# TouScruino-avr-v0.net
KiCad netlist of a schematic drawn in EAGLE
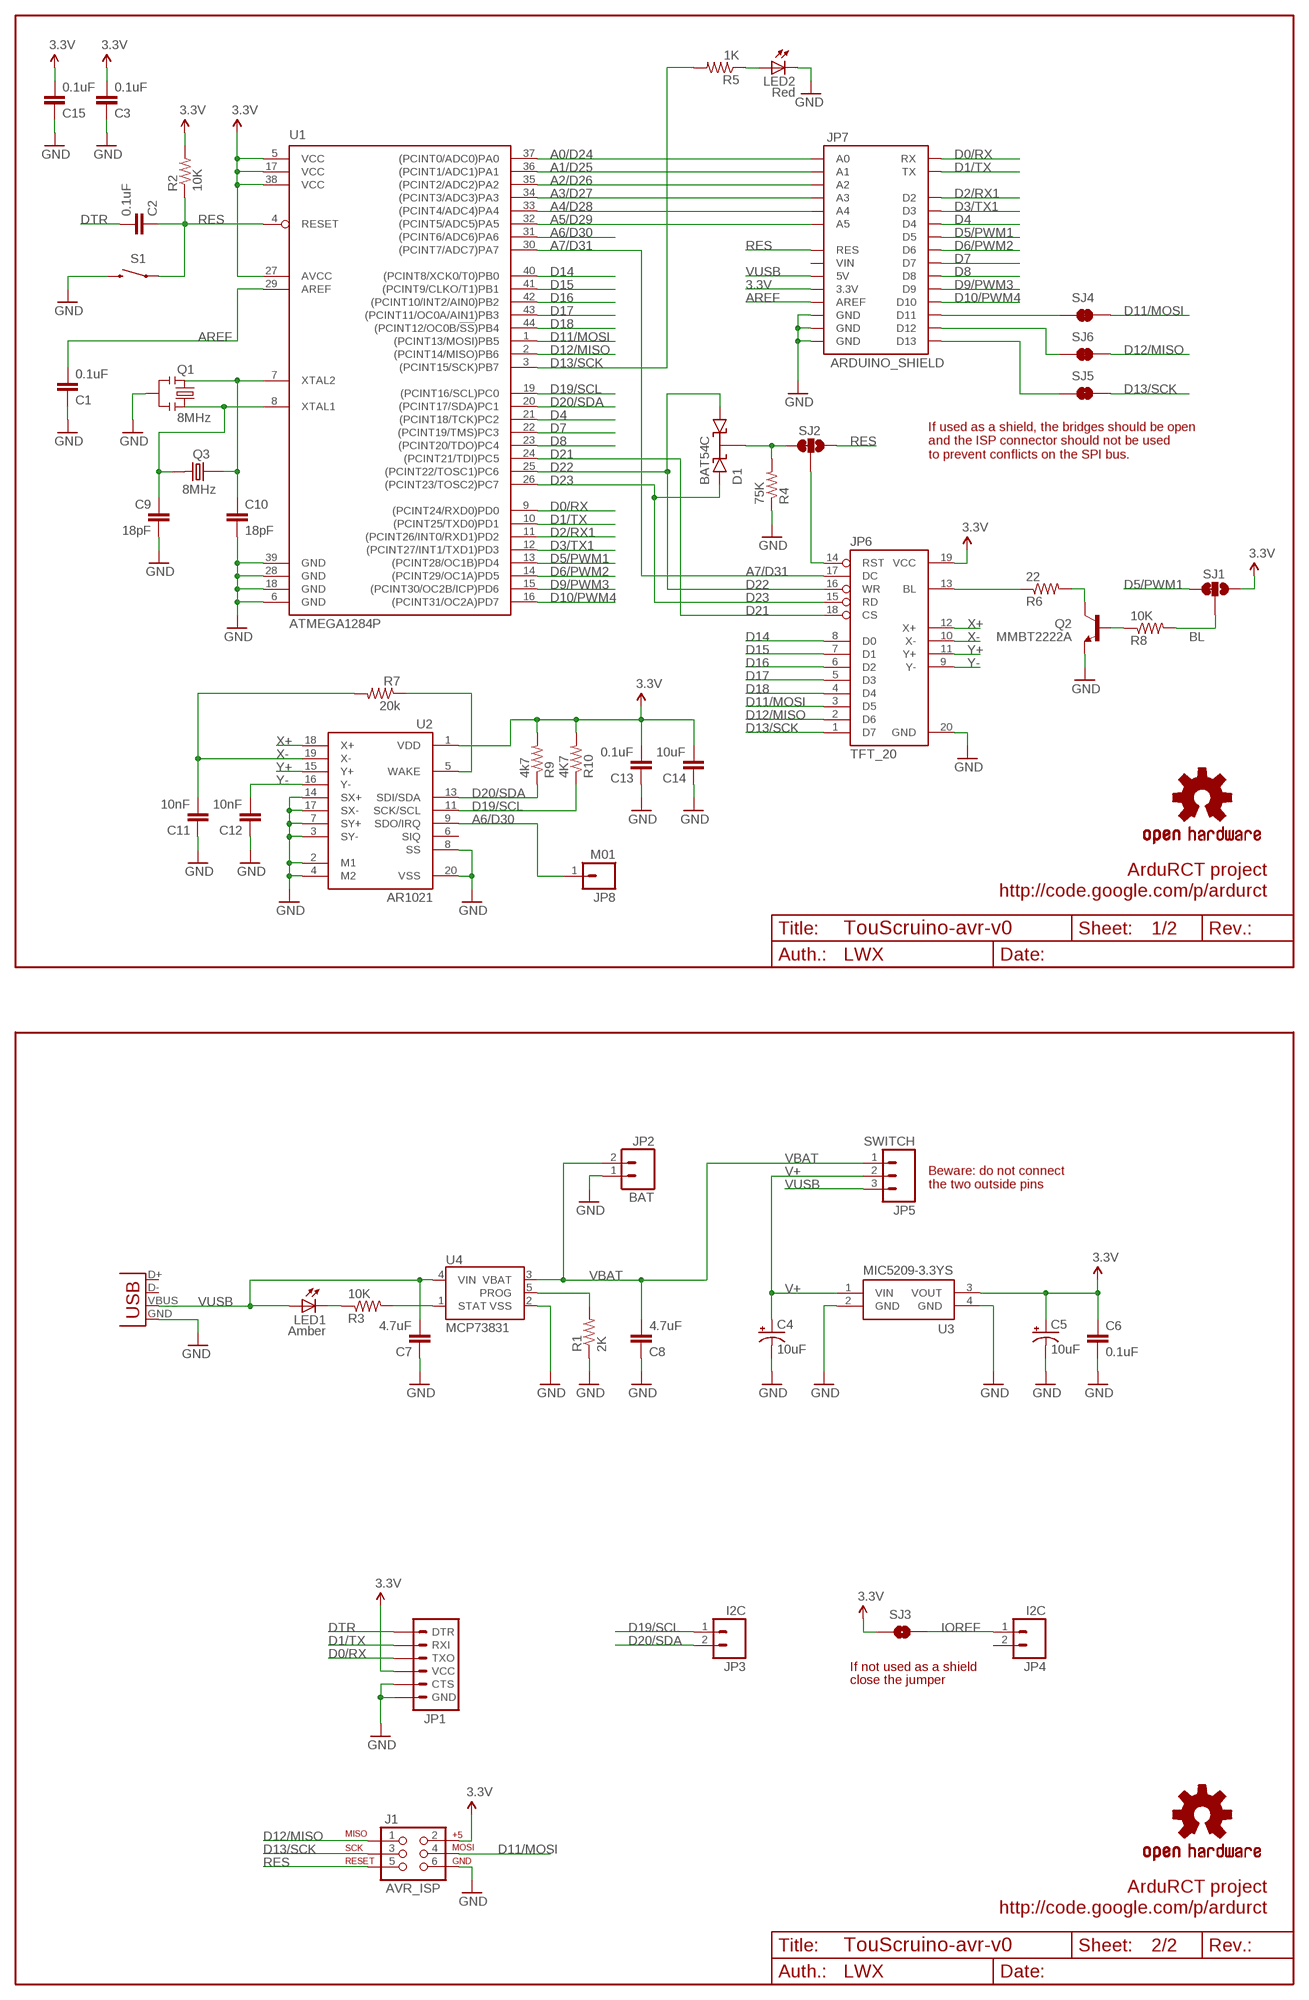
[diagram p0: schematic, sheet 1]

(export (version "E")
  (design (tool "Eeschema 10.0.6"))
  (components
    (comp (ref "C1")
      (value "0.1uF")
      (footprint "eagle-import:0805")
      (libsource (lib "eagle-import") (part "CAP0805"))
    )
    (comp (ref "C2")
      (value "0.1uF")
      (footprint "eagle-import:0805")
      (libsource (lib "eagle-import") (part "CAP0805"))
    )
    (comp (ref "C3")
      (value "0.1uF")
      (footprint "eagle-import:0805")
      (libsource (lib "eagle-import") (part "CAP0805"))
    )
    (comp (ref "C4")
      (value "10uF")
      (footprint "eagle-import:EIA3216")
      (libsource (lib "eagle-import") (part "CAP_POL1206"))
    )
    (comp (ref "C5")
      (value "10uF")
      (footprint "eagle-import:EIA3216")
      (libsource (lib "eagle-import") (part "CAP_POL1206"))
    )
    (comp (ref "C6")
      (value "0.1uF")
      (footprint "eagle-import:0805")
      (libsource (lib "eagle-import") (part "CAP0805"))
    )
    (comp (ref "C7")
      (value "4.7uF")
      (footprint "eagle-import:0805")
      (libsource (lib "eagle-import") (part "CAP0805"))
    )
    (comp (ref "C8")
      (value "4.7uF")
      (footprint "eagle-import:0805")
      (libsource (lib "eagle-import") (part "CAP0805"))
    )
    (comp (ref "C9")
      (value "18pF")
      (footprint "eagle-import:0603-CAP")
      (libsource (lib "eagle-import") (part "CAP0603-CAP"))
    )
    (comp (ref "C10")
      (value "18pF")
      (footprint "eagle-import:0603-CAP")
      (libsource (lib "eagle-import") (part "CAP0603-CAP"))
    )
    (comp (ref "C11")
      (value "10nF")
      (footprint "eagle-import:0805")
      (libsource (lib "eagle-import") (part "CAP0805"))
    )
    (comp (ref "C12")
      (value "10nF")
      (footprint "eagle-import:0805")
      (libsource (lib "eagle-import") (part "CAP0805"))
    )
    (comp (ref "C13")
      (value "0.1uF")
      (footprint "eagle-import:0805")
      (libsource (lib "eagle-import") (part "CAP0805"))
    )
    (comp (ref "C14")
      (value "10uF")
      (footprint "eagle-import:0805")
      (libsource (lib "eagle-import") (part "CAP0805"))
    )
    (comp (ref "C15")
      (value "0.1uF")
      (footprint "eagle-import:0805")
      (libsource (lib "eagle-import") (part "CAP0805"))
    )
    (comp (ref "D1")
      (value "BAT54C")
      (footprint "eagle-import:SOT23-3")
      (libsource (lib "eagle-import") (part "BAT54C"))
    )
    (comp (ref "J1")
      (value "AVR_ISP")
      (footprint "eagle-import:2X3")
      (libsource (lib "eagle-import") (part "AVR_SPI_PRG_6PTH"))
    )
    (comp (ref "JP1")
      (value "ARDUINO_SERIAL_PROGRAMPTH")
      (footprint "eagle-import:1X06")
      (libsource (lib "eagle-import") (part "ARDUINO_SERIAL_PROGRAMPTH"))
    )
    (comp (ref "JP2")
      (value "BAT")
      (footprint "eagle-import:JST-2-SMD")
      (libsource (lib "eagle-import") (part "M02-JST-2MM-SMT"))
    )
    (comp (ref "JP3")
      (value "I2C")
      (footprint "eagle-import:1X02")
      (libsource (lib "eagle-import") (part "M02"))
    )
    (comp (ref "JP4")
      (value "I2C")
      (footprint "eagle-import:1X02")
      (libsource (lib "eagle-import") (part "M02"))
    )
    (comp (ref "JP5")
      (value "SWITCH")
      (footprint "eagle-import:1X3_LONGPAD")
      (libsource (lib "eagle-import") (part "M03"))
    )
    (comp (ref "JP6")
      (value "TFT_20")
      (footprint "eagle-import:TFT_20")
      (libsource (lib "eagle-import") (part "TFT_20"))
    )
    (comp (ref "JP7")
      (value "ARDUINO_SHIELD")
      (footprint "eagle-import:ARDUINO_SHIELD")
      (libsource (lib "eagle-import") (part "ARDUINO_SHIELD"))
    )
    (comp (ref "JP8")
      (value "M01")
      (footprint "eagle-import:1X1")
      (libsource (lib "eagle-import") (part "M01"))
    )
    (comp (ref "LED1")
      (value "Amber")
      (footprint "eagle-import:LED")
      (libsource (lib "eagle-import") (part "LED"))
    )
    (comp (ref "LED2")
      (value "Red")
      (footprint "eagle-import:LED")
      (libsource (lib "eagle-import") (part "LED"))
    )
    (comp (ref "Q1")
      (value "8MHz")
      (footprint "eagle-import:RESONATOR-SMD")
      (libsource (lib "eagle-import") (part "RESONATORSMD"))
    )
    (comp (ref "Q2")
      (value "MMBT2222A")
      (footprint "eagle-import:SOT23-3")
      (libsource (lib "eagle-import") (part "TRANSISTOR_NPNSOT23-3"))
    )
    (comp (ref "Q3")
      (value "8MHz")
      (footprint "eagle-import:CRYSTAL_5X3.2")
      (libsource (lib "eagle-import") (part "CRYSTAL_5X3.2"))
    )
    (comp (ref "R1")
      (value "2K")
      (footprint "eagle-import:0805")
      (libsource (lib "eagle-import") (part "RESISTOR0805-RES"))
    )
    (comp (ref "R2")
      (value "10K")
      (footprint "eagle-import:0805")
      (libsource (lib "eagle-import") (part "RESISTOR0805-RES"))
    )
    (comp (ref "R3")
      (value "10K")
      (footprint "eagle-import:0805")
      (libsource (lib "eagle-import") (part "RESISTOR0805-RES"))
    )
    (comp (ref "R4")
      (value "75K")
      (footprint "eagle-import:0805")
      (libsource (lib "eagle-import") (part "RESISTOR0805-RES"))
    )
    (comp (ref "R5")
      (value "1K")
      (footprint "eagle-import:0805")
      (libsource (lib "eagle-import") (part "RESISTOR0805-RES"))
    )
    (comp (ref "R6")
      (value "22")
      (footprint "eagle-import:0805")
      (libsource (lib "eagle-import") (part "RESISTOR0805-RES"))
    )
    (comp (ref "R7")
      (value "20k")
      (footprint "eagle-import:0805")
      (libsource (lib "eagle-import") (part "RESISTOR0805-RES"))
    )
    (comp (ref "R8")
      (value "10K")
      (footprint "eagle-import:0805")
      (libsource (lib "eagle-import") (part "RESISTOR0805-RES"))
    )
    (comp (ref "R9")
      (value "4k7")
      (footprint "eagle-import:0805")
      (libsource (lib "eagle-import") (part "RESISTOR0805-RES"))
    )
    (comp (ref "R10")
      (value "4K7")
      (footprint "eagle-import:0805")
      (libsource (lib "eagle-import") (part "RESISTOR0805-RES"))
    )
    (comp (ref "S1")
      (value "SWITCH-MOMENTARY-2SMD")
      (footprint "eagle-import:TACTILE_SWITCH_SMD")
      (libsource (lib "eagle-import") (part "SWITCH-MOMENTARY-2SMD"))
    )
    (comp (ref "SJ1")
      (value "SJ_2WAYS_1-2")
      (footprint "eagle-import:SJ_2WAYS_1-2_S")
      (libsource (lib "eagle-import") (part "SJ_2WAYS_1-2"))
    )
    (comp (ref "SJ2")
      (value "SJ_2WAYS_1-2")
      (footprint "eagle-import:SJ_2WAYS_1-2_S")
      (libsource (lib "eagle-import") (part "SJ_2WAYS_1-2"))
    )
    (comp (ref "SJ3")
      (value "SOLDERJUMPERNO")
      (footprint "eagle-import:SJ_2S-NO")
      (libsource (lib "eagle-import") (part "SOLDERJUMPERNO"))
    )
    (comp (ref "SJ4")
      (value "SOLDERJUMPERTRACE")
      (footprint "eagle-import:SJ_2S-TRACE")
      (libsource (lib "eagle-import") (part "SOLDERJUMPERTRACE"))
    )
    (comp (ref "SJ5")
      (value "SOLDERJUMPERTRACE")
      (footprint "eagle-import:SJ_2S-TRACE")
      (libsource (lib "eagle-import") (part "SOLDERJUMPERTRACE"))
    )
    (comp (ref "SJ6")
      (value "SOLDERJUMPERTRACE")
      (footprint "eagle-import:SJ_2S-TRACE")
      (libsource (lib "eagle-import") (part "SOLDERJUMPERTRACE"))
    )
    (comp (ref "U$3")
      (value "OSHW-LOGOM")
      (footprint "eagle-import:OSHW-LOGO-M")
      (libsource (lib "eagle-import") (part "OSHW-LOGOM"))
    )
    (comp (ref "U$5")
      (value "OSHW-LOGOM")
      (footprint "eagle-import:OSHW-LOGO-M")
      (libsource (lib "eagle-import") (part "OSHW-LOGOM"))
    )
    (comp (ref "U1")
      (value "ATMEGA1284P")
      (footprint "eagle-import:TQFP44")
      (libsource (lib "eagle-import") (part "ATMEGA324A"))
    )
    (comp (ref "U2")
      (value "AR1021")
      (footprint "eagle-import:SSOP20")
      (libsource (lib "eagle-import") (part "AR1020"))
    )
    (comp (ref "U3")
      (value "MIC5209-3.3YS")
      (footprint "eagle-import:SOT223")
      (libsource (lib "eagle-import") (part "MIC5209"))
    )
    (comp (ref "U4")
      (value "MCP73831")
      (footprint "eagle-import:SOT23-5")
      (libsource (lib "eagle-import") (part "MCP73831"))
    )
    (comp (ref "X2")
      (value "USB-MICROB")
      (footprint "eagle-import:USB-MICROB")
      (libsource (lib "eagle-import") (part "USB-MICROB"))
    )
  )
  (nets
    (net (code "1") (name "/A0{slash}D24") (class "Default")
      (node (ref "JP7") (pin "A0") (pinfunction "A0_A0") (pintype "bidirectional"))
      (node (ref "U1") (pin "37") (pinfunction "(PCINT0/ADC0)PA0_37") (pintype "bidirectional"))
    )
    (net (code "2") (name "/A1{slash}D25") (class "Default")
      (node (ref "JP7") (pin "A1") (pinfunction "A1_A1") (pintype "bidirectional"))
      (node (ref "U1") (pin "36") (pinfunction "(PCINT1/ADC1)PA1_36") (pintype "bidirectional"))
    )
    (net (code "3") (name "/A2{slash}D26") (class "Default")
      (node (ref "JP7") (pin "A2") (pinfunction "A2_A2") (pintype "bidirectional"))
      (node (ref "U1") (pin "35") (pinfunction "(PCINT2/ADC2)PA2_35") (pintype "bidirectional"))
    )
    (net (code "4") (name "/A3{slash}D27") (class "Default")
      (node (ref "JP7") (pin "A3") (pinfunction "A3_A3") (pintype "bidirectional"))
      (node (ref "U1") (pin "34") (pinfunction "(PCINT3/ADC3)PA3_34") (pintype "bidirectional"))
    )
    (net (code "5") (name "/A4{slash}D28") (class "Default")
      (node (ref "JP7") (pin "A4") (pinfunction "A4_A4") (pintype "bidirectional"))
      (node (ref "U1") (pin "33") (pinfunction "(PCINT4/ADC4)PA4_33") (pintype "bidirectional"))
    )
    (net (code "6") (name "/A5{slash}D29") (class "Default")
      (node (ref "JP7") (pin "A5") (pinfunction "A5_A5") (pintype "bidirectional"))
      (node (ref "U1") (pin "32") (pinfunction "(PCINT5/ADC5)PA5_32") (pintype "bidirectional"))
    )
    (net (code "7") (name "/A6{slash}D30") (class "Default")
      (node (ref "JP8") (pin "1") (pinfunction "1_1") (pintype "passive"))
      (node (ref "U1") (pin "31") (pinfunction "(PCINT6/ADC6)PA6_31") (pintype "bidirectional"))
      (node (ref "U2") (pin "9") (pinfunction "SDO/IRQ_9") (pintype "bidirectional"))
    )
    (net (code "8") (name "/A7{slash}D31") (class "Default")
      (node (ref "JP6") (pin "17") (pinfunction "DC_17") (pintype "bidirectional"))
      (node (ref "U1") (pin "30") (pinfunction "(PCINT7/ADC7)PA7_30") (pintype "bidirectional"))
    )
    (net (code "9") (name "/AREF") (class "Default")
      (node (ref "C1") (pin "2") (pinfunction "2_2") (pintype "passive"))
      (node (ref "JP7") (pin "AREF") (pinfunction "AREF_AREF") (pintype "bidirectional"))
      (node (ref "U1") (pin "29") (pinfunction "AREF_29") (pintype "passive"))
    )
    (net (code "10") (name "/BL") (class "Default")
      (node (ref "R8") (pin "2") (pinfunction "2_2") (pintype "passive"))
      (node (ref "SJ1") (pin "2") (pinfunction "2_2") (pintype "passive"))
    )
    (net (code "11") (name "/D0{slash}RX") (class "Default")
      (node (ref "JP1") (pin "3") (pinfunction "TXO_3") (pintype "passive"))
      (node (ref "JP7") (pin "RX") (pinfunction "RX_RX") (pintype "bidirectional"))
      (node (ref "U1") (pin "9") (pinfunction "(PCINT24/RXD0)PD0_9") (pintype "bidirectional"))
    )
    (net (code "12") (name "/D1{slash}TX") (class "Default")
      (node (ref "JP1") (pin "2") (pinfunction "RXI_2") (pintype "passive"))
      (node (ref "JP7") (pin "TX") (pinfunction "TX_TX") (pintype "bidirectional"))
      (node (ref "U1") (pin "10") (pinfunction "(PCINT25/TXD0)PD1_10") (pintype "bidirectional"))
    )
    (net (code "13") (name "/D2{slash}RX1") (class "Default")
      (node (ref "JP7") (pin "D2") (pinfunction "D2_D2") (pintype "bidirectional"))
      (node (ref "U1") (pin "11") (pinfunction "(PCINT26/INT0/RXD1)PD2_11") (pintype "bidirectional"))
    )
    (net (code "14") (name "/D3{slash}TX1") (class "Default")
      (node (ref "JP7") (pin "D3") (pinfunction "D3_D3") (pintype "bidirectional"))
      (node (ref "U1") (pin "12") (pinfunction "(PCINT27/INT1/TXD1)PD3_12") (pintype "bidirectional"))
    )
    (net (code "15") (name "/D4") (class "Default")
      (node (ref "JP7") (pin "D4") (pinfunction "D4_D4") (pintype "bidirectional"))
      (node (ref "U1") (pin "21") (pinfunction "(PCINT18/TCK)PC2_21") (pintype "output"))
    )
    (net (code "16") (name "/D5{slash}PWM1") (class "Default")
      (node (ref "JP7") (pin "D5") (pinfunction "D5_D5") (pintype "bidirectional"))
      (node (ref "SJ1") (pin "1") (pinfunction "1_1") (pintype "passive"))
      (node (ref "U1") (pin "13") (pinfunction "(PCINT28/OC1B)PD4_13") (pintype "bidirectional"))
    )
    (net (code "17") (name "/D6{slash}PWM2") (class "Default")
      (node (ref "JP7") (pin "D6") (pinfunction "D6_D6") (pintype "bidirectional"))
      (node (ref "U1") (pin "14") (pinfunction "(PCINT29/OC1A)PD5_14") (pintype "bidirectional"))
    )
    (net (code "18") (name "/D7") (class "Default")
      (node (ref "JP7") (pin "D7") (pinfunction "D7_D7") (pintype "bidirectional"))
      (node (ref "U1") (pin "22") (pinfunction "(PCINT19/TMS)PC3_22") (pintype "output"))
    )
    (net (code "19") (name "/D8") (class "Default")
      (node (ref "JP7") (pin "D8") (pinfunction "D8_D8") (pintype "bidirectional"))
      (node (ref "U1") (pin "23") (pinfunction "(PCINT20/TDO)PC4_23") (pintype "output"))
    )
    (net (code "20") (name "/D9{slash}PWM3") (class "Default")
      (node (ref "JP7") (pin "D9") (pinfunction "D9_D9") (pintype "bidirectional"))
      (node (ref "U1") (pin "15") (pinfunction "(PCINT30/OC2B/ICP)PD6_15") (pintype "bidirectional"))
    )
    (net (code "21") (name "/D10{slash}PWM4") (class "Default")
      (node (ref "JP7") (pin "D10") (pinfunction "D10_D10") (pintype "bidirectional"))
      (node (ref "U1") (pin "16") (pinfunction "(PCINT31/OC2A)PD7_16") (pintype "bidirectional"))
    )
    (net (code "22") (name "/D11{slash}MOSI") (class "Default")
      (node (ref "J1") (pin "4") (pinfunction "4_4") (pintype "passive"))
      (node (ref "JP6") (pin "3") (pinfunction "D5_3") (pintype "bidirectional"))
      (node (ref "SJ4") (pin "2") (pinfunction "2_2") (pintype "passive"))
      (node (ref "U1") (pin "1") (pinfunction "(PCINT13/MOSI)PB5_1") (pintype "bidirectional"))
    )
    (net (code "23") (name "/D12{slash}MISO") (class "Default")
      (node (ref "J1") (pin "1") (pinfunction "1_1") (pintype "passive"))
      (node (ref "JP6") (pin "2") (pinfunction "D6_2") (pintype "bidirectional"))
      (node (ref "SJ6") (pin "2") (pinfunction "2_2") (pintype "passive"))
      (node (ref "U1") (pin "2") (pinfunction "(PCINT14/MISO)PB6_2") (pintype "bidirectional"))
    )
    (net (code "24") (name "/D13{slash}SCK") (class "Default")
      (node (ref "J1") (pin "3") (pinfunction "3_3") (pintype "passive"))
      (node (ref "JP6") (pin "1") (pinfunction "D7_1") (pintype "bidirectional"))
      (node (ref "R5") (pin "2") (pinfunction "2_2") (pintype "passive"))
      (node (ref "SJ5") (pin "2") (pinfunction "2_2") (pintype "passive"))
      (node (ref "U1") (pin "3") (pinfunction "(PCINT15/SCK)PB7_3") (pintype "bidirectional"))
    )
    (net (code "25") (name "/D14") (class "Default")
      (node (ref "JP6") (pin "8") (pinfunction "D0_8") (pintype "bidirectional"))
      (node (ref "U1") (pin "40") (pinfunction "(PCINT8/XCK0/T0)PB0_40") (pintype "bidirectional"))
    )
    (net (code "26") (name "/D15") (class "Default")
      (node (ref "JP6") (pin "7") (pinfunction "D1_7") (pintype "bidirectional"))
      (node (ref "U1") (pin "41") (pinfunction "(PCINT9/CLKO/T1)PB1_41") (pintype "bidirectional"))
    )
    (net (code "27") (name "/D16") (class "Default")
      (node (ref "JP6") (pin "6") (pinfunction "D2_6") (pintype "bidirectional"))
      (node (ref "U1") (pin "42") (pinfunction "(PCINT10/INT2/AIN0)PB2_42") (pintype "bidirectional"))
    )
    (net (code "28") (name "/D17") (class "Default")
      (node (ref "JP6") (pin "5") (pinfunction "D3_5") (pintype "bidirectional"))
      (node (ref "U1") (pin "43") (pinfunction "(PCINT11/OC0A/AIN1)PB3_43") (pintype "bidirectional"))
    )
    (net (code "29") (name "/D18") (class "Default")
      (node (ref "JP6") (pin "4") (pinfunction "D4_4") (pintype "bidirectional"))
      (node (ref "U1") (pin "44") (pinfunction "(PCINT12/OC0B/~{SS})PB4_44") (pintype "bidirectional"))
    )
    (net (code "30") (name "/D19{slash}SCL") (class "Default")
      (node (ref "JP3") (pin "1") (pinfunction "1_1") (pintype "passive"))
      (node (ref "R10") (pin "1") (pinfunction "1_1") (pintype "passive"))
      (node (ref "U1") (pin "19") (pinfunction "(PCINT16/SCL)PC0_19") (pintype "output"))
      (node (ref "U2") (pin "11") (pinfunction "SCK/SCL_11") (pintype "bidirectional"))
    )
    (net (code "31") (name "/D20{slash}SDA") (class "Default")
      (node (ref "JP3") (pin "2") (pinfunction "2_2") (pintype "passive"))
      (node (ref "R9") (pin "1") (pinfunction "1_1") (pintype "passive"))
      (node (ref "U1") (pin "20") (pinfunction "(PCINT17/SDA)PC1_20") (pintype "output"))
      (node (ref "U2") (pin "13") (pinfunction "SDI/SDA_13") (pintype "bidirectional"))
    )
    (net (code "32") (name "/D21") (class "Default")
      (node (ref "JP6") (pin "18") (pinfunction "CS_18") (pintype "bidirectional"))
      (node (ref "U1") (pin "24") (pinfunction "(PCINT21/TDI)PC5_24") (pintype "output"))
    )
    (net (code "33") (name "/D22") (class "Default")
      (node (ref "D1") (pin "1") (pinfunction "A1_1") (pintype "bidirectional"))
      (node (ref "JP6") (pin "16") (pinfunction "WR_16") (pintype "bidirectional"))
      (node (ref "U1") (pin "25") (pinfunction "(PCINT22/TOSC1)PC6_25") (pintype "output"))
    )
    (net (code "34") (name "/D23") (class "Default")
      (node (ref "D1") (pin "2") (pinfunction "A2_2") (pintype "bidirectional"))
      (node (ref "JP6") (pin "15") (pinfunction "RD_15") (pintype "bidirectional"))
      (node (ref "U1") (pin "26") (pinfunction "(PCINT23/TOSC2)PC7_26") (pintype "output"))
    )
    (net (code "35") (name "/DTR") (class "Default")
      (node (ref "C2") (pin "2") (pinfunction "2_2") (pintype "passive"))
      (node (ref "JP1") (pin "1") (pinfunction "DTR_1") (pintype "passive"))
    )
    (net (code "36") (name "/IOREF") (class "Default")
      (node (ref "JP4") (pin "1") (pinfunction "1_1") (pintype "passive"))
      (node (ref "SJ3") (pin "2") (pinfunction "2_2") (pintype "passive"))
    )
    (net (code "37") (name "/RES") (class "Default")
      (node (ref "C2") (pin "1") (pinfunction "1_1") (pintype "passive"))
      (node (ref "J1") (pin "5") (pinfunction "5_5") (pintype "passive"))
      (node (ref "JP7") (pin "RES") (pinfunction "RES_RES") (pintype "bidirectional"))
      (node (ref "R2") (pin "1") (pinfunction "1_1") (pintype "passive"))
      (node (ref "S1") (pin "1") (pinfunction "1_1") (pintype "passive"))
      (node (ref "SJ2") (pin "3") (pinfunction "3_3") (pintype "passive"))
      (node (ref "U1") (pin "4") (pinfunction "RESET_4") (pintype "input"))
    )
    (net (code "38") (name "/V+") (class "Default")
      (node (ref "C4") (pin "A") (pinfunction "+_A") (pintype "passive"))
      (node (ref "JP5") (pin "2") (pinfunction "2_2") (pintype "passive"))
      (node (ref "U3") (pin "1") (pinfunction "VIN_1") (pintype "bidirectional"))
    )
    (net (code "39") (name "/VBAT") (class "Default")
      (node (ref "C8") (pin "2") (pinfunction "2_2") (pintype "passive"))
      (node (ref "JP2") (pin "2") (pinfunction "2_2") (pintype "passive"))
      (node (ref "JP5") (pin "1") (pinfunction "1_1") (pintype "passive"))
      (node (ref "U4") (pin "3") (pinfunction "VBAT_3") (pintype "power_in"))
    )
    (net (code "40") (name "/VUSB") (class "Default")
      (node (ref "C7") (pin "2") (pinfunction "2_2") (pintype "passive"))
      (node (ref "JP5") (pin "3") (pinfunction "3_3") (pintype "passive"))
      (node (ref "JP7") (pin "5V") (pinfunction "5V_5V") (pintype "bidirectional"))
      (node (ref "LED1") (pin "A1") (pinfunction "A_A1") (pintype "passive"))
      (node (ref "U4") (pin "4") (pinfunction "VIN_4") (pintype "power_in"))
      (node (ref "X2") (pin "VBUS") (pinfunction "VBUS_VBUS") (pintype "bidirectional"))
    )
    (net (code "41") (name "/X+") (class "Default")
      (node (ref "JP6") (pin "12") (pinfunction "X+_12") (pintype "bidirectional"))
      (node (ref "U2") (pin "18") (pinfunction "X+_18") (pintype "bidirectional"))
    )
    (net (code "42") (name "/X-") (class "Default")
      (node (ref "C11") (pin "2") (pinfunction "2_2") (pintype "passive"))
      (node (ref "JP6") (pin "10") (pinfunction "X-_10") (pintype "bidirectional"))
      (node (ref "R7") (pin "2") (pinfunction "2_2") (pintype "passive"))
      (node (ref "U2") (pin "19") (pinfunction "X-_19") (pintype "bidirectional"))
    )
    (net (code "43") (name "/Y+") (class "Default")
      (node (ref "JP6") (pin "11") (pinfunction "Y+_11") (pintype "bidirectional"))
      (node (ref "U2") (pin "15") (pinfunction "Y+_15") (pintype "bidirectional"))
    )
    (net (code "44") (name "/Y-") (class "Default")
      (node (ref "C12") (pin "2") (pinfunction "2_2") (pintype "passive"))
      (node (ref "JP6") (pin "9") (pinfunction "Y-_9") (pintype "bidirectional"))
      (node (ref "U2") (pin "16") (pinfunction "Y-_16") (pintype "bidirectional"))
    )
    (net (code "45") (name "3.3V") (class "Default")
      (node (ref "C13") (pin "2") (pinfunction "2_2") (pintype "passive"))
      (node (ref "C14") (pin "2") (pinfunction "2_2") (pintype "passive"))
      (node (ref "C15") (pin "2") (pinfunction "2_2") (pintype "passive"))
      (node (ref "C3") (pin "2") (pinfunction "2_2") (pintype "passive"))
      (node (ref "C5") (pin "A") (pinfunction "+_A") (pintype "passive"))
      (node (ref "C6") (pin "1") (pinfunction "1_1") (pintype "passive"))
      (node (ref "J1") (pin "2") (pinfunction "2_2") (pintype "passive"))
      (node (ref "JP1") (pin "4") (pinfunction "VCC_4") (pintype "passive"))
      (node (ref "JP6") (pin "19") (pinfunction "VCC_19") (pintype "bidirectional"))
      (node (ref "JP7") (pin "3.3V") (pinfunction "3.3V_3.3V") (pintype "bidirectional"))
      (node (ref "R10") (pin "2") (pinfunction "2_2") (pintype "passive"))
      (node (ref "R2") (pin "2") (pinfunction "2_2") (pintype "passive"))
      (node (ref "R9") (pin "2") (pinfunction "2_2") (pintype "passive"))
      (node (ref "SJ1") (pin "3") (pinfunction "3_3") (pintype "passive"))
      (node (ref "SJ3") (pin "1") (pinfunction "1_1") (pintype "passive"))
      (node (ref "U1") (pin "17") (pinfunction "VCC_17") (pintype "power_in"))
      (node (ref "U1") (pin "27") (pinfunction "AVCC_27") (pintype "power_in"))
      (node (ref "U1") (pin "38") (pinfunction "VCC_38") (pintype "power_in"))
      (node (ref "U1") (pin "5") (pinfunction "VCC_5") (pintype "power_in"))
      (node (ref "U2") (pin "1") (pinfunction "VDD_1") (pintype "bidirectional"))
      (node (ref "U3") (pin "3") (pinfunction "VOUT_3") (pintype "bidirectional"))
    )
    (net (code "46") (name "GND") (class "Default")
      (node (ref "C1") (pin "1") (pinfunction "1_1") (pintype "passive"))
      (node (ref "C10") (pin "2") (pinfunction "2_2") (pintype "passive"))
      (node (ref "C11") (pin "1") (pinfunction "1_1") (pintype "passive"))
      (node (ref "C12") (pin "1") (pinfunction "1_1") (pintype "passive"))
      (node (ref "C13") (pin "1") (pinfunction "1_1") (pintype "passive"))
      (node (ref "C14") (pin "1") (pinfunction "1_1") (pintype "passive"))
      (node (ref "C15") (pin "1") (pinfunction "1_1") (pintype "passive"))
      (node (ref "C3") (pin "1") (pinfunction "1_1") (pintype "passive"))
      (node (ref "C4") (pin "C") (pinfunction "-_C") (pintype "passive"))
      (node (ref "C5") (pin "C") (pinfunction "-_C") (pintype "passive"))
      (node (ref "C6") (pin "2") (pinfunction "2_2") (pintype "passive"))
      (node (ref "C7") (pin "1") (pinfunction "1_1") (pintype "passive"))
      (node (ref "C8") (pin "1") (pinfunction "1_1") (pintype "passive"))
      (node (ref "C9") (pin "2") (pinfunction "2_2") (pintype "passive"))
      (node (ref "J1") (pin "6") (pinfunction "6_6") (pintype "passive"))
      (node (ref "JP1") (pin "5") (pinfunction "CTS_5") (pintype "passive"))
      (node (ref "JP1") (pin "6") (pinfunction "GND_6") (pintype "passive"))
      (node (ref "JP2") (pin "1") (pinfunction "1_1") (pintype "passive"))
      (node (ref "JP6") (pin "20") (pinfunction "GND_20") (pintype "bidirectional"))
      (node (ref "JP7") (pin "GND@0") (pinfunction "GND_GND@0") (pintype "bidirectional"))
      (node (ref "JP7") (pin "GND@1") (pinfunction "GND_GND@1") (pintype "bidirectional"))
      (node (ref "JP7") (pin "GND@2") (pinfunction "GND_GND@2") (pintype "bidirectional"))
      (node (ref "LED2") (pin "C1") (pinfunction "C_C1") (pintype "passive"))
      (node (ref "Q1") (pin "2") (pinfunction "2_2") (pintype "passive"))
      (node (ref "Q2") (pin "2") (pinfunction "E_2") (pintype "passive"))
      (node (ref "R1") (pin "1") (pinfunction "1_1") (pintype "passive"))
      (node (ref "R4") (pin "1") (pinfunction "1_1") (pintype "passive"))
      (node (ref "S1") (pin "3") (pinfunction "2_3") (pintype "passive"))
      (node (ref "U1") (pin "18") (pinfunction "GND_18") (pintype "power_in"))
      (node (ref "U1") (pin "28") (pinfunction "GND_28") (pintype "power_in"))
      (node (ref "U1") (pin "39") (pinfunction "GND_39") (pintype "power_in"))
      (node (ref "U1") (pin "6") (pinfunction "GND_6") (pintype "power_in"))
      (node (ref "U2") (pin "14") (pinfunction "SX+_14") (pintype "bidirectional"))
      (node (ref "U2") (pin "17") (pinfunction "SX-_17") (pintype "bidirectional"))
      (node (ref "U2") (pin "2") (pinfunction "M1_2") (pintype "bidirectional"))
      (node (ref "U2") (pin "20") (pinfunction "VSS_20") (pintype "bidirectional"))
      (node (ref "U2") (pin "3") (pinfunction "SY-_3") (pintype "bidirectional"))
      (node (ref "U2") (pin "4") (pinfunction "M2_4") (pintype "bidirectional"))
      (node (ref "U2") (pin "7") (pinfunction "SY+_7") (pintype "bidirectional"))
      (node (ref "U2") (pin "8") (pinfunction "SS_8") (pintype "bidirectional"))
      (node (ref "U3") (pin "2") (pinfunction "GND_2") (pintype "bidirectional"))
      (node (ref "U3") (pin "4") (pinfunction "GND_4") (pintype "bidirectional"))
      (node (ref "U4") (pin "2") (pinfunction "VSS_2") (pintype "power_in"))
      (node (ref "X2") (pin "GND") (pinfunction "GND_GND") (pintype "bidirectional"))
    )
    (net (code "47") (name "Net-(D1-K)") (class "Default")
      (node (ref "D1") (pin "3") (pinfunction "K_3") (pintype "bidirectional"))
      (node (ref "R4") (pin "2") (pinfunction "2_2") (pintype "passive"))
      (node (ref "SJ2") (pin "1") (pinfunction "1_1") (pintype "passive"))
    )
    (net (code "48") (name "Net-(JP6-BL)") (class "Default")
      (node (ref "JP6") (pin "13") (pinfunction "BL_13") (pintype "bidirectional"))
      (node (ref "R6") (pin "1") (pinfunction "1_1") (pintype "passive"))
    )
    (net (code "49") (name "Net-(JP6-RST)") (class "Default")
      (node (ref "JP6") (pin "14") (pinfunction "RST_14") (pintype "bidirectional"))
      (node (ref "SJ2") (pin "2") (pinfunction "2_2") (pintype "passive"))
    )
    (net (code "50") (name "Net-(JP7-PadD11)") (class "Default")
      (node (ref "JP7") (pin "D11") (pinfunction "D11_D11") (pintype "bidirectional"))
      (node (ref "SJ4") (pin "1") (pinfunction "1_1") (pintype "passive"))
    )
    (net (code "51") (name "Net-(JP7-PadD12)") (class "Default")
      (node (ref "JP7") (pin "D12") (pinfunction "D12_D12") (pintype "bidirectional"))
      (node (ref "SJ6") (pin "1") (pinfunction "1_1") (pintype "passive"))
    )
    (net (code "52") (name "Net-(JP7-PadD13)") (class "Default")
      (node (ref "JP7") (pin "D13") (pinfunction "D13_D13") (pintype "bidirectional"))
      (node (ref "SJ5") (pin "1") (pinfunction "1_1") (pintype "passive"))
    )
    (net (code "53") (name "Net-(LED1-C)") (class "Default")
      (node (ref "LED1") (pin "C1") (pinfunction "C_C1") (pintype "passive"))
      (node (ref "R3") (pin "1") (pinfunction "1_1") (pintype "passive"))
    )
    (net (code "54") (name "Net-(LED2-A)") (class "Default")
      (node (ref "LED2") (pin "A1") (pinfunction "A_A1") (pintype "passive"))
      (node (ref "R5") (pin "1") (pinfunction "1_1") (pintype "passive"))
    )
    (net (code "55") (name "Net-(Q2-B)") (class "Default")
      (node (ref "Q2") (pin "1") (pinfunction "B_1") (pintype "passive"))
      (node (ref "R8") (pin "1") (pinfunction "1_1") (pintype "passive"))
    )
    (net (code "56") (name "Net-(Q2-C)") (class "Default")
      (node (ref "Q2") (pin "3") (pinfunction "C_3") (pintype "passive"))
      (node (ref "R6") (pin "2") (pinfunction "2_2") (pintype "passive"))
    )
    (net (code "57") (name "Net-(U1-XTAL1)") (class "Default")
      (node (ref "C9") (pin "1") (pinfunction "1_1") (pintype "passive"))
      (node (ref "Q1") (pin "1") (pinfunction "1_1") (pintype "passive"))
      (node (ref "Q3") (pin "2") (pinfunction "2_2") (pintype "passive"))
      (node (ref "U1") (pin "8") (pinfunction "XTAL1_8") (pintype "bidirectional"))
    )
    (net (code "58") (name "Net-(U1-XTAL2)") (class "Default")
      (node (ref "C10") (pin "1") (pinfunction "1_1") (pintype "passive"))
      (node (ref "Q1") (pin "3") (pinfunction "3_3") (pintype "passive"))
      (node (ref "Q3") (pin "1") (pinfunction "1_1") (pintype "passive"))
      (node (ref "U1") (pin "7") (pinfunction "XTAL2_7") (pintype "bidirectional"))
    )
    (net (code "59") (name "Net-(U2-WAKE)") (class "Default")
      (node (ref "R7") (pin "1") (pinfunction "1_1") (pintype "passive"))
      (node (ref "U2") (pin "5") (pinfunction "WAKE_5") (pintype "bidirectional"))
    )
    (net (code "60") (name "Net-(U4-PROG)") (class "Default")
      (node (ref "R1") (pin "2") (pinfunction "2_2") (pintype "passive"))
      (node (ref "U4") (pin "5") (pinfunction "PROG_5") (pintype "input"))
    )
    (net (code "61") (name "Net-(U4-STAT)") (class "Default")
      (node (ref "R3") (pin "2") (pinfunction "2_2") (pintype "passive"))
      (node (ref "U4") (pin "1") (pinfunction "STAT_1") (pintype "output"))
    )
    (net (code "62") (name "unconnected-(JP4-Pad2)") (class "Default")
      (node (ref "JP4") (pin "2") (pinfunction "2_2") (pintype "passive"))
    )
    (net (code "63") (name "unconnected-(JP7-PadVIN)") (class "Default")
      (node (ref "JP7") (pin "VIN") (pinfunction "VIN_VIN") (pintype "bidirectional"))
    )
    (net (code "64") (name "unconnected-(U2-SIQ-Pad6)") (class "Default")
      (node (ref "U2") (pin "6") (pinfunction "SIQ_6") (pintype "bidirectional"))
    )
    (net (code "65") (name "unconnected-(X2-PadD+)") (class "Default")
      (node (ref "X2") (pin "D+") (pinfunction "D+_D+") (pintype "bidirectional"))
    )
    (net (code "66") (name "unconnected-(X2-PadD-)") (class "Default")
      (node (ref "X2") (pin "D-") (pinfunction "D-_D-") (pintype "bidirectional"))
    )
  )
)
